# Clock_looser.net
KiCad netlist of a schematic drawn in EAGLE
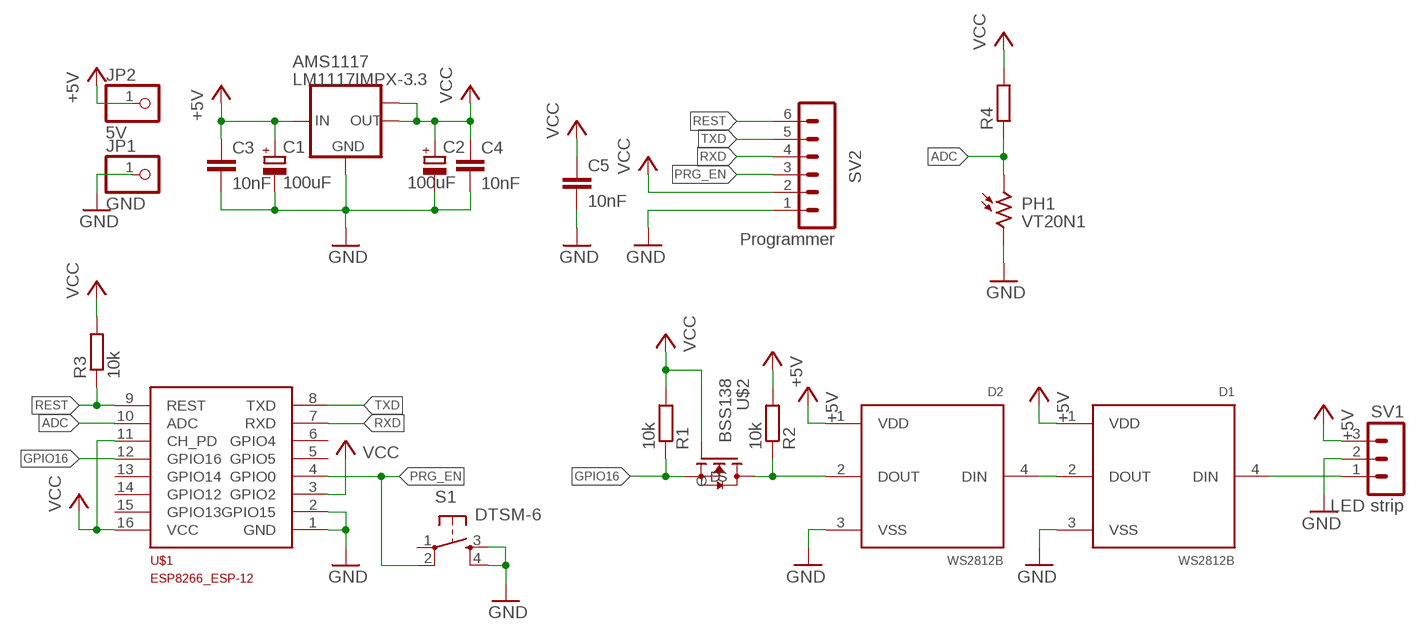
[diagram p0: schematic, sheet 1]

(export (version "E")
  (design (tool "Eeschema 10.0.6"))
  (components
    (comp (ref "AMS1117")
      (value "LM1117IMPX-3.3")
      (footprint "eagle-import:SOT223")
      (libsource (lib "eagle-import") (part "LM1117IMPX-3.3"))
    )
    (comp (ref "C1")
      (value "100uF")
      (footprint "eagle-import:TT5D7L")
      (libsource (lib "eagle-import") (part "CPOL-EUTT5D7L"))
    )
    (comp (ref "C2")
      (value "100uF")
      (footprint "eagle-import:TT5D7L")
      (libsource (lib "eagle-import") (part "CPOL-EUTT5D7L"))
    )
    (comp (ref "C3")
      (value "10nF")
      (footprint "eagle-import:C0805")
      (libsource (lib "eagle-import") (part "C-EUC0805"))
    )
    (comp (ref "C4")
      (value "10nF")
      (footprint "eagle-import:C0805")
      (libsource (lib "eagle-import") (part "C-EUC0805"))
    )
    (comp (ref "C5")
      (value "10nF")
      (footprint "eagle-import:C0805")
      (libsource (lib "eagle-import") (part "C-EUC0805"))
    )
    (comp (ref "D1")
      (value "WS2812B")
      (footprint "eagle-import:LED_WS2812B")
      (fields (field (name "MF") "Adafruit Industries"))
      (libsource (lib "eagle-import") (part "WS2812B"))
    )
    (comp (ref "D2")
      (value "WS2812B")
      (footprint "eagle-import:LED_WS2812B")
      (fields (field (name "MF") "Adafruit Industries"))
      (libsource (lib "eagle-import") (part "WS2812B"))
    )
    (comp (ref "JP1")
      (value "GND")
      (footprint "eagle-import:1X01")
      (libsource (lib "eagle-import") (part "PINHD-1X1"))
    )
    (comp (ref "JP2")
      (value "5V")
      (footprint "eagle-import:1X01")
      (libsource (lib "eagle-import") (part "PINHD-1X1"))
    )
    (comp (ref "PH1")
      (value "VT20N1")
      (footprint "eagle-import:TO46-VT200")
      (libsource (lib "eagle-import") (part "VT20N1"))
    )
    (comp (ref "R1")
      (value "10k")
      (footprint "eagle-import:R0805")
      (libsource (lib "eagle-import") (part "R-EU_R0805"))
    )
    (comp (ref "R2")
      (value "10k")
      (footprint "eagle-import:R0805")
      (libsource (lib "eagle-import") (part "R-EU_R0805"))
    )
    (comp (ref "R3")
      (value "10k")
      (footprint "eagle-import:R0805")
      (libsource (lib "eagle-import") (part "R-EU_R0805"))
    )
    (comp (ref "R4")
      (value "R-EU_R0805")
      (footprint "eagle-import:R0805")
      (libsource (lib "eagle-import") (part "R-EU_R0805"))
    )
    (comp (ref "S1")
      (value "DTSM-6")
      (footprint "eagle-import:DTSM-6")
      (libsource (lib "eagle-import") (part "DTSM-6"))
    )
    (comp (ref "SV1")
      (value "LED strip")
      (footprint "eagle-import:MA03-1")
      (libsource (lib "eagle-import") (part "MA03-1"))
    )
    (comp (ref "SV2")
      (value "Programmer")
      (footprint "eagle-import:MA06-1")
      (libsource (lib "eagle-import") (part "MA06-1"))
    )
    (comp (ref "U$1")
      (value "ESP8266_ESP-12")
      (footprint "eagle-import:ESP8266-ESP12")
      (libsource (lib "eagle-import") (part "ESP8266_ESP-12"))
    )
    (comp (ref "U$2")
      (value "BSS138")
      (footprint "eagle-import:BSS138")
      (fields (field (name "MF") "Fairchild Semiconductor"))
      (libsource (lib "eagle-import") (part "BSS138"))
    )
  )
  (nets
    (net (code "1") (name "+5V") (class "Default")
      (node (ref "AMS1117") (pin "3") (pinfunction "IN_3") (pintype "input"))
      (node (ref "C1") (pin "+") (pinfunction "+_+") (pintype "passive"))
      (node (ref "C3") (pin "1") (pinfunction "1_1") (pintype "passive"))
      (node (ref "D1") (pin "1") (pinfunction "VDD_1") (pintype "power_in"))
      (node (ref "D2") (pin "1") (pinfunction "VDD_1") (pintype "power_in"))
      (node (ref "JP2") (pin "1") (pinfunction "1_1") (pintype "passive"))
      (node (ref "R2") (pin "2") (pinfunction "2_2") (pintype "passive"))
      (node (ref "SV1") (pin "3") (pinfunction "3_3") (pintype "passive"))
    )
    (net (code "2") (name "ADC") (class "Default")
      (node (ref "PH1") (pin "1") (pinfunction "1_1") (pintype "passive"))
      (node (ref "R4") (pin "1") (pinfunction "1_1") (pintype "passive"))
      (node (ref "U$1") (pin "10") (pinfunction "ADC_10") (pintype "bidirectional"))
    )
    (net (code "3") (name "GND") (class "Default")
      (node (ref "AMS1117") (pin "1") (pinfunction "GND_1") (pintype "input"))
      (node (ref "C1") (pin "-") (pinfunction "-_-") (pintype "passive"))
      (node (ref "C2") (pin "-") (pinfunction "-_-") (pintype "passive"))
      (node (ref "C3") (pin "2") (pinfunction "2_2") (pintype "passive"))
      (node (ref "C4") (pin "2") (pinfunction "2_2") (pintype "passive"))
      (node (ref "C5") (pin "2") (pinfunction "2_2") (pintype "passive"))
      (node (ref "D1") (pin "3") (pinfunction "VSS_3") (pintype "passive"))
      (node (ref "D2") (pin "3") (pinfunction "VSS_3") (pintype "passive"))
      (node (ref "JP1") (pin "1") (pinfunction "1_1") (pintype "passive"))
      (node (ref "PH1") (pin "2") (pinfunction "2_2") (pintype "passive"))
      (node (ref "S1") (pin "3") (pinfunction "3_3") (pintype "passive"))
      (node (ref "S1") (pin "4") (pinfunction "4_4") (pintype "passive"))
      (node (ref "SV1") (pin "2") (pinfunction "2_2") (pintype "passive"))
      (node (ref "SV2") (pin "1") (pinfunction "1_1") (pintype "passive"))
      (node (ref "U$1") (pin "1") (pinfunction "GND_1") (pintype "bidirectional"))
      (node (ref "U$1") (pin "2") (pinfunction "GPIO15_2") (pintype "bidirectional"))
    )
    (net (code "4") (name "GPIO16") (class "Default")
      (node (ref "R1") (pin "1") (pinfunction "1_1") (pintype "passive"))
      (node (ref "U$1") (pin "12") (pinfunction "GPIO16_12") (pintype "bidirectional"))
      (node (ref "U$2") (pin "S") (pinfunction "S_S") (pintype "passive"))
    )
    (net (code "5") (name "Net-(D1-DIN)") (class "Default")
      (node (ref "D1") (pin "4") (pinfunction "DIN_4") (pintype "input"))
      (node (ref "SV1") (pin "1") (pinfunction "1_1") (pintype "passive"))
    )
    (net (code "6") (name "Net-(D1-DOUT)") (class "Default")
      (node (ref "D1") (pin "2") (pinfunction "DOUT_2") (pintype "output"))
      (node (ref "D2") (pin "4") (pinfunction "DIN_4") (pintype "input"))
    )
    (net (code "7") (name "Net-(D2-DOUT)") (class "Default")
      (node (ref "D2") (pin "2") (pinfunction "DOUT_2") (pintype "output"))
      (node (ref "R2") (pin "1") (pinfunction "1_1") (pintype "passive"))
      (node (ref "U$2") (pin "D") (pinfunction "D_D") (pintype "passive"))
    )
    (net (code "8") (name "PRG_EN") (class "Default")
      (node (ref "S1") (pin "2") (pinfunction "2_2") (pintype "passive"))
      (node (ref "SV2") (pin "3") (pinfunction "3_3") (pintype "passive"))
      (node (ref "U$1") (pin "4") (pinfunction "GPIO0_4") (pintype "bidirectional"))
    )
    (net (code "9") (name "REST") (class "Default")
      (node (ref "R3") (pin "1") (pinfunction "1_1") (pintype "passive"))
      (node (ref "SV2") (pin "6") (pinfunction "6_6") (pintype "passive"))
      (node (ref "U$1") (pin "9") (pinfunction "REST_9") (pintype "bidirectional"))
    )
    (net (code "10") (name "RXD") (class "Default")
      (node (ref "SV2") (pin "4") (pinfunction "4_4") (pintype "passive"))
      (node (ref "U$1") (pin "7") (pinfunction "RXD_7") (pintype "bidirectional"))
    )
    (net (code "11") (name "TXD") (class "Default")
      (node (ref "SV2") (pin "5") (pinfunction "5_5") (pintype "passive"))
      (node (ref "U$1") (pin "8") (pinfunction "TXD_8") (pintype "bidirectional"))
    )
    (net (code "12") (name "VCC") (class "Default")
      (node (ref "AMS1117") (pin "2") (pinfunction "OUT_2") (pintype "passive"))
      (node (ref "AMS1117") (pin "TAB") (pinfunction "OUT1_TAB") (pintype "passive"))
      (node (ref "C2") (pin "+") (pinfunction "+_+") (pintype "passive"))
      (node (ref "C4") (pin "1") (pinfunction "1_1") (pintype "passive"))
      (node (ref "C5") (pin "1") (pinfunction "1_1") (pintype "passive"))
      (node (ref "R1") (pin "2") (pinfunction "2_2") (pintype "passive"))
      (node (ref "R3") (pin "2") (pinfunction "2_2") (pintype "passive"))
      (node (ref "R4") (pin "2") (pinfunction "2_2") (pintype "passive"))
      (node (ref "SV2") (pin "2") (pinfunction "2_2") (pintype "passive"))
      (node (ref "U$1") (pin "11") (pinfunction "CH_PD_11") (pintype "bidirectional"))
      (node (ref "U$1") (pin "16") (pinfunction "VCC_16") (pintype "bidirectional"))
      (node (ref "U$1") (pin "3") (pinfunction "GPIO2_3") (pintype "bidirectional"))
      (node (ref "U$2") (pin "G") (pinfunction "G_G") (pintype "passive"))
    )
    (net (code "13") (name "unconnected-(S1-Pad1)") (class "Default")
      (node (ref "S1") (pin "1") (pinfunction "1_1") (pintype "passive"))
    )
    (net (code "14") (name "unconnected-(U$1-GPIO4-Pad6)") (class "Default")
      (node (ref "U$1") (pin "6") (pinfunction "GPIO4_6") (pintype "bidirectional"))
    )
    (net (code "15") (name "unconnected-(U$1-GPIO5-Pad5)") (class "Default")
      (node (ref "U$1") (pin "5") (pinfunction "GPIO5_5") (pintype "bidirectional"))
    )
    (net (code "16") (name "unconnected-(U$1-GPIO12-Pad14)") (class "Default")
      (node (ref "U$1") (pin "14") (pinfunction "GPIO12_14") (pintype "bidirectional"))
    )
    (net (code "17") (name "unconnected-(U$1-GPIO13-Pad15)") (class "Default")
      (node (ref "U$1") (pin "15") (pinfunction "GPIO13_15") (pintype "bidirectional"))
    )
    (net (code "18") (name "unconnected-(U$1-GPIO14-Pad13)") (class "Default")
      (node (ref "U$1") (pin "13") (pinfunction "GPIO14_13") (pintype "bidirectional"))
    )
  )
)
